# Data_Conversion.net
KiCad netlist of a schematic drawn in Altium Designer
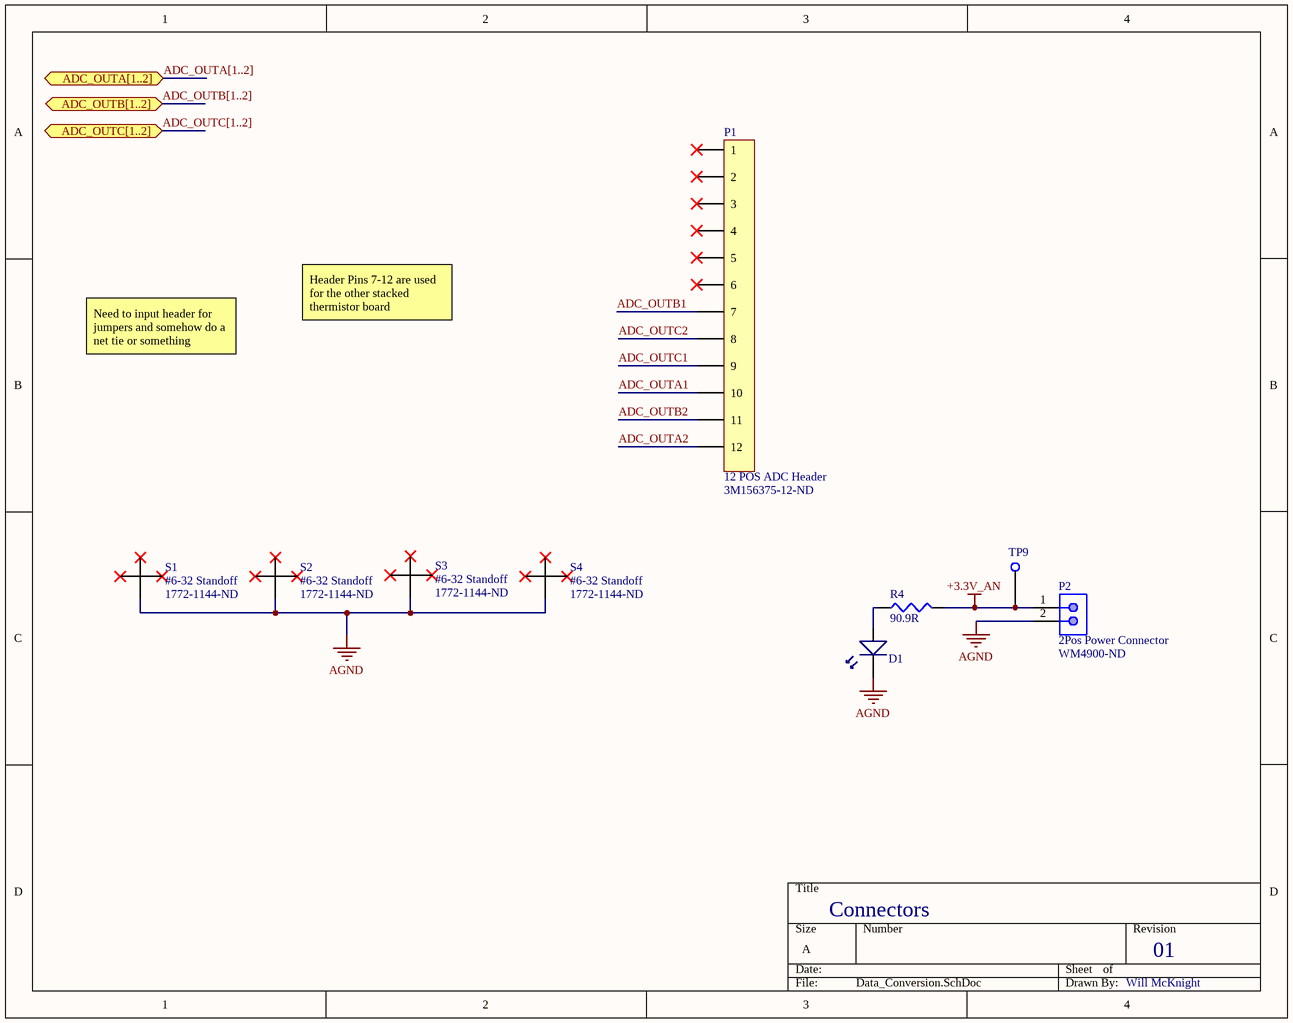
[diagram p0: Data_Conversion.SchDoc]

(export (version "E")
  (design (tool "Eeschema 10.0.6"))
  (components
    (comp (ref "D1")
      (value "LED")
      (footprint "Green_SMD_LED")
      (fields
        (field (name "MANUFACTURER") "Dialight")
        (field (name "MANUFACTURER PART NUMBER") "5988070107F")
      )
      (libsource (lib "Schematic_Library") (part "GREEN_LED"))
    )
    (comp (ref "P1")
      (value "12 POS ADC Header")
      (footprint "12 POS Dual Header")
      (description "Interboard connector for thermistors connecting to ADC")
      (fields
        (field (name "MANUFACTURER") "3M")
        (field (name "MANUFACTURER PART NUMBER") "929715-06-06-EU")
        (field (name "SUPPLIER PART NUMBER 1") "3M156375-12-ND")
      )
      (libsource (lib "Schematic_Library") (part "12 POS ADC Header"))
    )
    (comp (ref "P2")
      (value "2Pos Power Connector")
      (footprint "2Pos Power Connector")
      (description "Headers & Wire Housings R/A HDR 2P low profile single")
      (fields
        (field (name "MANUFACTURER") "Molex")
        (field (name "MANUFACTURER PART NUMBER") "70553-0001")
        (field (name "SUPPLIER PART NUMBER 1") "WM4900-ND")
      )
      (libsource (lib "Schematic_Library") (part "2Pos Power Connector"))
    )
    (comp (ref "R4")
      (value "Green")
      (footprint "Green_LED_Resistor_90.9")
      (fields
        (field (name "MANUFACTURER") "Panasonic")
        (field (name "MANUFACTURER PART NUMBER") "ERJ-1GNF90R9C")
        (field (name "TOLERANCE") "1%")
        (field (name "RESISTANCE") "90.9R")
      )
      (libsource (lib "Schematic_Library") (part "Green_LED_Res"))
    )
    (comp (ref "S1")
      (value "#6-32 Standoff")
      (footprint "#6-32 Stand Off")
      (description "Hex Standoff for Thermistor Boards")
      (fields
        (field (name "MANUFACTURER") "RAF")
        (field (name "MANUFACTURER PART NUMBER") "2102T-632-AL-7")
        (field (name "SUPPLIER PART NUMBER 1") "1772-1144-ND")
      )
      (libsource (lib "Schematic_Library") (part "#6-32 Standoff"))
    )
    (comp (ref "S2")
      (value "#6-32 Standoff")
      (footprint "#6-32 Stand Off")
      (description "Hex Standoff for Thermistor Boards")
      (fields
        (field (name "MANUFACTURER") "RAF")
        (field (name "MANUFACTURER PART NUMBER") "2102T-632-AL-7")
        (field (name "SUPPLIER PART NUMBER 1") "1772-1144-ND")
      )
      (libsource (lib "Schematic_Library") (part "#6-32 Standoff"))
    )
    (comp (ref "S3")
      (value "#6-32 Standoff")
      (footprint "#6-32 Stand Off")
      (description "Hex Standoff for Thermistor Boards")
      (fields
        (field (name "MANUFACTURER") "RAF")
        (field (name "MANUFACTURER PART NUMBER") "2102T-632-AL-7")
        (field (name "SUPPLIER PART NUMBER 1") "1772-1144-ND")
      )
      (libsource (lib "Schematic_Library") (part "#6-32 Standoff"))
    )
    (comp (ref "S4")
      (value "#6-32 Standoff")
      (footprint "#6-32 Stand Off")
      (description "Hex Standoff for Thermistor Boards")
      (fields
        (field (name "MANUFACTURER") "RAF")
        (field (name "MANUFACTURER PART NUMBER") "2102T-632-AL-7")
        (field (name "SUPPLIER PART NUMBER 1") "1772-1144-ND")
      )
      (libsource (lib "Schematic_Library") (part "#6-32 Standoff"))
    )
    (comp (ref "TP9")
      (value "Test Point")
      (footprint "Test Point")
      (libsource (lib "Schematic_Library") (part "Test Point"))
    )
  )
  (nets
    (net (code "1") (name "+3.3V_AN") (class "Default")
      (node (ref "P2") (pin "1") (pinfunction "1_1") (pintype "passive"))
      (node (ref "R4") (pin "2") (pinfunction "2_2") (pintype "passive"))
      (node (ref "TP9") (pin "1") (pinfunction "1_1") (pintype "passive"))
    )
    (net (code "2") (name "/ADC_OUTA1") (class "Default")
      (node (ref "P1") (pin "10") (pinfunction "10_10") (pintype "passive"))
    )
    (net (code "3") (name "/ADC_OUTA2") (class "Default")
      (node (ref "P1") (pin "12") (pinfunction "12_12") (pintype "passive"))
    )
    (net (code "5") (name "/ADC_OUTB1") (class "Default")
      (node (ref "P1") (pin "7") (pinfunction "7_7") (pintype "passive"))
    )
    (net (code "6") (name "/ADC_OUTB2") (class "Default")
      (node (ref "P1") (pin "11") (pinfunction "11_11") (pintype "passive"))
    )
    (net (code "8") (name "/ADC_OUTC1") (class "Default")
      (node (ref "P1") (pin "9") (pinfunction "9_9") (pintype "passive"))
    )
    (net (code "9") (name "/ADC_OUTC2") (class "Default")
      (node (ref "P1") (pin "8") (pinfunction "8_8") (pintype "passive"))
    )
    (net (code "11") (name "AGND") (class "Default")
      (node (ref "D1") (pin "1") (pinfunction "1_1") (pintype "passive"))
      (node (ref "P2") (pin "2") (pinfunction "2_2") (pintype "passive"))
      (node (ref "S1") (pin "1") (pinfunction "2_1") (pintype "passive"))
      (node (ref "S2") (pin "1") (pinfunction "2_1") (pintype "passive"))
      (node (ref "S3") (pin "1") (pinfunction "2_1") (pintype "passive"))
      (node (ref "S4") (pin "1") (pinfunction "2_1") (pintype "passive"))
    )
    (net (code "12") (name "Net-(D1-Pad2)") (class "Default")
      (node (ref "D1") (pin "2") (pinfunction "2_2") (pintype "passive"))
      (node (ref "R4") (pin "1") (pinfunction "1_1") (pintype "passive"))
    )
    (net (code "13") (name "unconnected-(P1-Pad1)") (class "Default")
      (node (ref "P1") (pin "1") (pinfunction "1_1") (pintype "passive+no_connect"))
    )
    (net (code "14") (name "unconnected-(P1-Pad2)") (class "Default")
      (node (ref "P1") (pin "2") (pinfunction "2_2") (pintype "passive+no_connect"))
    )
    (net (code "15") (name "unconnected-(P1-Pad3)") (class "Default")
      (node (ref "P1") (pin "3") (pinfunction "3_3") (pintype "passive+no_connect"))
    )
    (net (code "16") (name "unconnected-(P1-Pad4)") (class "Default")
      (node (ref "P1") (pin "4") (pinfunction "4_4") (pintype "passive+no_connect"))
    )
    (net (code "17") (name "unconnected-(P1-Pad5)") (class "Default")
      (node (ref "P1") (pin "5") (pinfunction "5_5") (pintype "passive+no_connect"))
    )
    (net (code "18") (name "unconnected-(P1-Pad6)") (class "Default")
      (node (ref "P1") (pin "6") (pinfunction "6_6") (pintype "passive+no_connect"))
    )
    (net (code "19") (name "unconnected-(S1-3-Pad1)") (class "Default")
      (node (ref "S1") (pin "1") (pinfunction "3_1") (pintype "passive+no_connect"))
    )
    (net (code "20") (name "unconnected-(S1-4-Pad1)") (class "Default")
      (node (ref "S1") (pin "1") (pinfunction "4_1") (pintype "passive+no_connect"))
    )
    (net (code "21") (name "unconnected-(S1-Pad1)") (class "Default")
      (node (ref "S1") (pin "1") (pinfunction "1_1") (pintype "passive+no_connect"))
    )
    (net (code "22") (name "unconnected-(S2-3-Pad1)") (class "Default")
      (node (ref "S2") (pin "1") (pinfunction "3_1") (pintype "passive+no_connect"))
    )
    (net (code "23") (name "unconnected-(S2-4-Pad1)") (class "Default")
      (node (ref "S2") (pin "1") (pinfunction "4_1") (pintype "passive+no_connect"))
    )
    (net (code "24") (name "unconnected-(S2-Pad1)") (class "Default")
      (node (ref "S2") (pin "1") (pinfunction "1_1") (pintype "passive+no_connect"))
    )
    (net (code "25") (name "unconnected-(S3-3-Pad1)") (class "Default")
      (node (ref "S3") (pin "1") (pinfunction "3_1") (pintype "passive+no_connect"))
    )
    (net (code "26") (name "unconnected-(S3-4-Pad1)") (class "Default")
      (node (ref "S3") (pin "1") (pinfunction "4_1") (pintype "passive+no_connect"))
    )
    (net (code "27") (name "unconnected-(S3-Pad1)") (class "Default")
      (node (ref "S3") (pin "1") (pinfunction "1_1") (pintype "passive+no_connect"))
    )
    (net (code "28") (name "unconnected-(S4-3-Pad1)") (class "Default")
      (node (ref "S4") (pin "1") (pinfunction "3_1") (pintype "passive+no_connect"))
    )
    (net (code "29") (name "unconnected-(S4-4-Pad1)") (class "Default")
      (node (ref "S4") (pin "1") (pinfunction "4_1") (pintype "passive+no_connect"))
    )
    (net (code "30") (name "unconnected-(S4-Pad1)") (class "Default")
      (node (ref "S4") (pin "1") (pinfunction "1_1") (pintype "passive+no_connect"))
    )
  )
)
